# Sheet2.net
KiCad netlist of a schematic drawn in Altium Designer
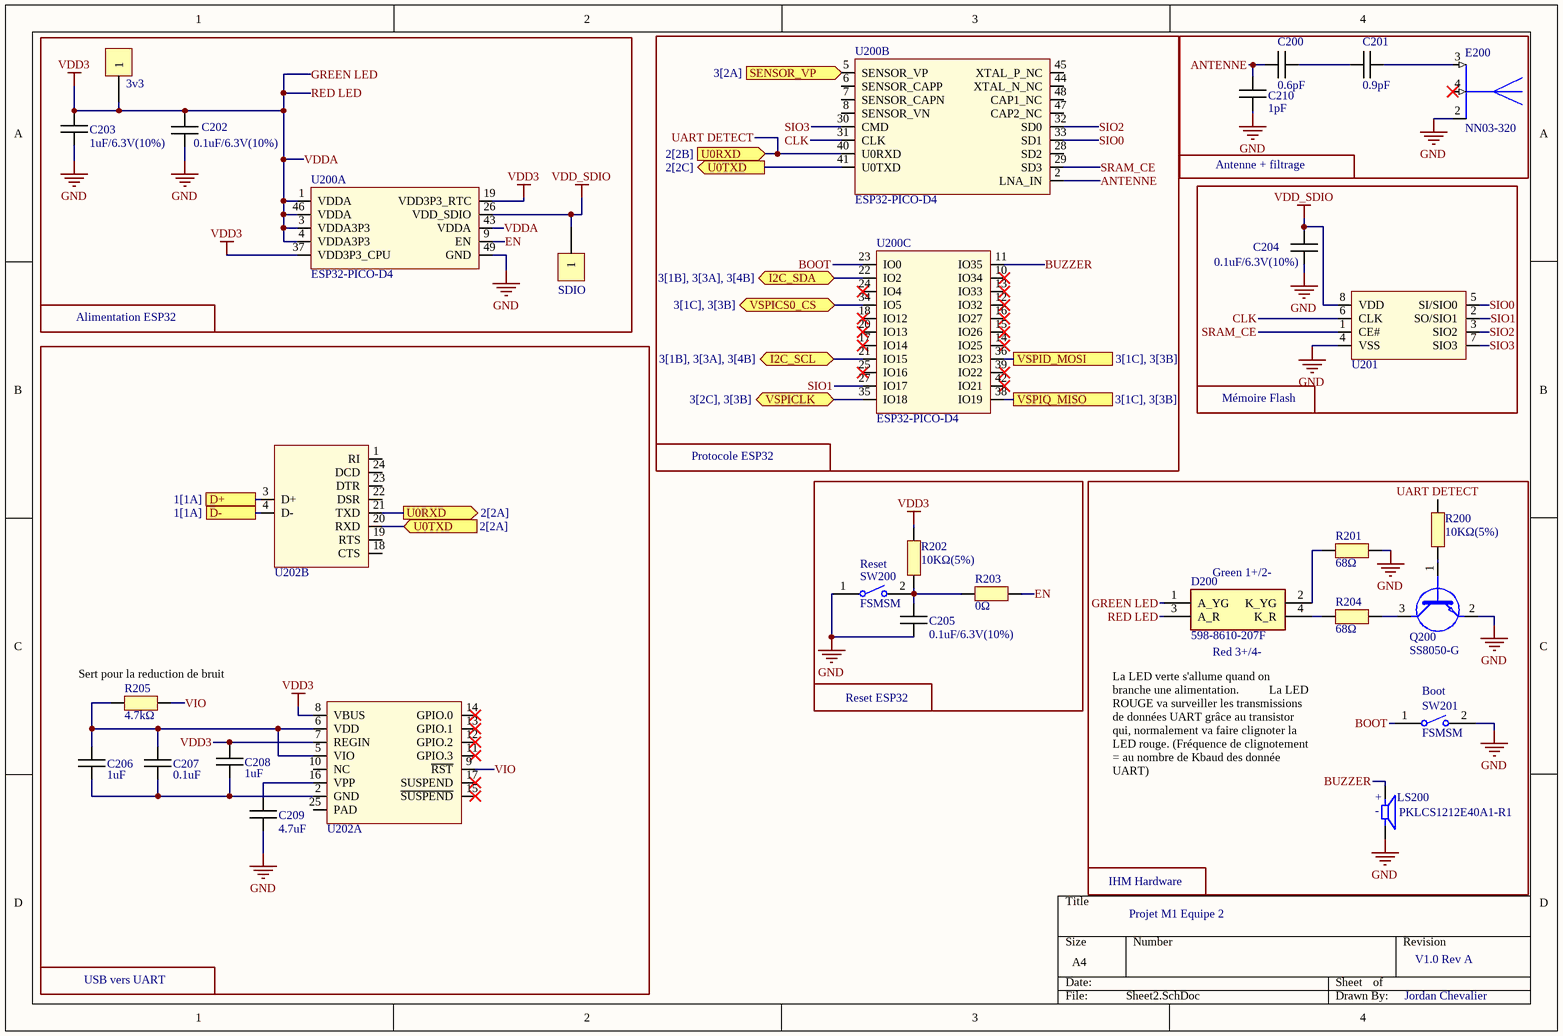
[diagram p0: Sheet2.SchDoc]

(export (version "E")
  (design (tool "Eeschema 10.0.6"))
  (components
    (comp (ref "3v3")
      (value "Plage CMS 10x5")
      (footprint "Plage CMS 10x5")
      (description "Plage de report CMS 10x5mm")
      (libsource (lib "") (part "Plage CMS 10x5_1"))
    )
    (comp (ref "C200")
      (value "0.6pF")
      (footprint "CAPC1005X06N")
      (libsource (lib "SCHLibrary") (part "Capacitor"))
    )
    (comp (ref "C201")
      (value "0.9pF")
      (footprint "CAPC1005X06N")
      (libsource (lib "SCHLibrary") (part "Capacitor"))
    )
    (comp (ref "C202")
      (value "0.1uF/6.3V(10%)")
      (footprint "CAPC1005X06N")
      (libsource (lib "SCHLibrary") (part "Capacitor"))
    )
    (comp (ref "C203")
      (value "1uF/6.3V(10%)")
      (footprint "CAPC1005X06N")
      (libsource (lib "SCHLibrary") (part "Capacitor"))
    )
    (comp (ref "C204")
      (value "0.1uF/6.3V(10%)")
      (footprint "CAPC1005X06N")
      (libsource (lib "SCHLibrary") (part "Capacitor"))
    )
    (comp (ref "C205")
      (value "0.1uF/6.3V(10%)")
      (footprint "CAPC1005X06N")
      (libsource (lib "SCHLibrary") (part "Capacitor"))
    )
    (comp (ref "C206")
      (value "1uF")
      (footprint "CAPC1005X06N")
      (libsource (lib "SCHLibrary") (part "Capacitor"))
    )
    (comp (ref "C207")
      (value "0.1uF")
      (footprint "CAPC1005X06N")
      (libsource (lib "SCHLibrary") (part "Capacitor"))
    )
    (comp (ref "C208")
      (value "1uF")
      (footprint "CAPC1005X06N")
      (libsource (lib "SCHLibrary") (part "Capacitor"))
    )
    (comp (ref "C209")
      (value "4.7uF")
      (footprint "CAPC1005X06N")
      (libsource (lib "SCHLibrary") (part "Capacitor"))
    )
    (comp (ref "C210")
      (value "1pF")
      (footprint "CAPC1005X06N")
      (libsource (lib "SCHLibrary") (part "Capacitor"))
    )
    (comp (ref "D200")
      (value "598-8610-207F")
      (footprint "5988610207F")
      (description "Standard LEDs - SMD Red/Green WC 80/50mcd 645/570nm")
      (fields (field (name "MOUSER PART NUMBER") "645-598-8610-207F"))
      (libsource (lib "SCHLibrary") (part "598-8610-207F"))
    )
    (comp (ref "E200")
      (value "NN03-320")
      (footprint "XCVR_NN03-320")
      (fields (field (name "MOUSER PART NUMBER") "128-NN03-320"))
      (libsource (lib "SCHLibrary") (part "NN03-320"))
    )
    (comp (ref "LS200")
      (value "PKLCS1212E40A1-R1")
      (footprint "SPKR_PKLCS1212E40A1-R1")
      (description "Buzzers Transducer, Externally Driven Piezo 1.5V 2kHz 70dB @ 1.5V, 10cm Surface Mount Solder Pads")
      (fields (field (name "MF") "Murata Electronics"))
      (libsource (lib "SCHLibrary") (part "PKLCS1212E40A1-R1"))
    )
    (comp (ref "Q200")
      (value "SS8050-G")
      (footprint "SS8050-G")
      (description "Bipolar Transistors - BJT NPN TRANSISTOR 1.5A 40V")
      (libsource (lib "SCHLibrary") (part "SS8050-G"))
    )
    (comp (ref "R200")
      (value "10KΩ(5%)")
      (footprint "RESC1005X06N")
      (libsource (lib "SCHLibrary") (part "Resistor"))
    )
    (comp (ref "R201") (value "68Ω") (footprint "RESC1005X06N") (libsource (lib "") (part "Resistor_1")))
    (comp (ref "R202")
      (value "10KΩ(5%)")
      (footprint "RESC1005X06N")
      (libsource (lib "SCHLibrary") (part "Resistor"))
    )
    (comp (ref "R203") (value "0Ω") (footprint "RESC1005X06N") (libsource (lib "") (part "Resistor_1")))
    (comp (ref "R204") (value "68Ω") (footprint "RESC1005X06N") (libsource (lib "") (part "Resistor_1")))
    (comp (ref "R205") (value "4.7kΩ") (footprint "RESC1005X06N") (libsource (lib "") (part "Resistor_1")))
    (comp (ref "SDIO")
      (value "Plage CMS 10x5")
      (footprint "Plage CMS 10x5")
      (description "Plage de report CMS 10x5mm")
      (libsource (lib "SCHLibrary") (part "Plage CMS 10x5"))
    )
    (comp (ref "SW200")
      (value "FSMSM")
      (footprint "TECO-FSMSM-2_V")
      (description "FSMSM Push Button Switch, 50 mA, -35 to 85 degC, 2-Pin SMD, RoHS, Bulk")
      (fields (field (name "MANUFACTURER") "TE Connectivity"))
      (libsource (lib "SCHLibrary") (part "CMP-2000-07511-1"))
    )
    (comp (ref "SW201")
      (value "FSMSM")
      (footprint "TECO-FSMSM-2_V")
      (description "FSMSM Push Button Switch, 50 mA, -35 to 85 degC, 2-Pin SMD, RoHS, Bulk")
      (fields (field (name "MANUFACTURER") "TE Connectivity"))
      (libsource (lib "SCHLibrary") (part "CMP-2000-07511-1"))
    )
    (comp (ref "U200")
      (value "ESP32-PICO-D4")
      (footprint "PQFN50P700X700X104_HS-49N")
      (libsource (lib "SCHLibrary") (part "ESP32"))
    )
    (comp (ref "U201")
      (value "IS66WVS1M8BLL-104NLI")
      (footprint "SOIC127P600X175-8N")
      (description "SRAM 8Mb, SerialRAM, 2.7V-3.6V, 104MHz, 8 pin SOIC 150 mil, RoHS")
      (libsource (lib "SCHLibrary") (part "SRAM"))
    )
    (comp (ref "U202")
      (value "CP2104-F03-GM")
      (footprint "PQFN50P400X400X80_HS-25N")
      (description "USB Bridge, USB to UART USB 2.0 UART Interface 24-QFN (4x4)")
      (libsource (lib "SCHLibrary") (part "USBBridge"))
    )
  )
  (nets
    (net (code "1") (name "/ANTENNE") (class "Default")
      (node (ref "C200") (pin "1") (pinfunction "1_1") (pintype "passive"))
      (node (ref "C210") (pin "1") (pinfunction "1_1") (pintype "passive"))
      (node (ref "U200") (pin "2") (pinfunction "LNA_IN_2") (pintype "passive"))
    )
    (net (code "2") (name "/BOOT") (class "Default")
      (node (ref "SW201") (pin "1") (pinfunction "1_1") (pintype "passive"))
      (node (ref "U200") (pin "23") (pinfunction "IO0_23") (pintype "passive"))
    )
    (net (code "3") (name "/BUZZER") (class "Default")
      (node (ref "LS200") (pin "P") (pinfunction "P_P") (pintype "passive"))
      (node (ref "U200") (pin "11") (pinfunction "IO35_11") (pintype "passive"))
    )
    (net (code "4") (name "/CLK") (class "Default")
      (node (ref "U200") (pin "31") (pinfunction "CLK_31") (pintype "passive"))
      (node (ref "U201") (pin "6") (pinfunction "CLK_6") (pintype "passive"))
    )
    (net (code "5") (name "/D+") (class "Default")
      (node (ref "U202") (pin "3") (pinfunction "D+_3") (pintype "passive"))
    )
    (net (code "6") (name "/D-") (class "Default")
      (node (ref "U202") (pin "4") (pinfunction "D-_4") (pintype "passive"))
    )
    (net (code "7") (name "/EN") (class "Default")
      (node (ref "R203") (pin "2") (pinfunction "2_2") (pintype "passive"))
      (node (ref "U200") (pin "9") (pinfunction "EN_9") (pintype "passive"))
    )
    (net (code "8") (name "/I2C_SCL") (class "Default")
      (node (ref "U200") (pin "21") (pinfunction "IO15_21") (pintype "passive"))
    )
    (net (code "9") (name "/I2C_SDA") (class "Default")
      (node (ref "U200") (pin "22") (pinfunction "IO2_22") (pintype "passive"))
    )
    (net (code "10") (name "/SENSOR_VP") (class "Default")
      (node (ref "U200") (pin "5") (pinfunction "SENSOR_VP_5") (pintype "passive"))
    )
    (net (code "11") (name "/SIO0") (class "Default")
      (node (ref "U200") (pin "33") (pinfunction "SD1_33") (pintype "passive"))
      (node (ref "U201") (pin "5") (pinfunction "SI/SIO0_5") (pintype "passive"))
    )
    (net (code "12") (name "/SIO1") (class "Default")
      (node (ref "U200") (pin "27") (pinfunction "IO17_27") (pintype "passive"))
      (node (ref "U201") (pin "2") (pinfunction "SO/SIO1_2") (pintype "passive"))
    )
    (net (code "13") (name "/SIO2") (class "Default")
      (node (ref "U200") (pin "32") (pinfunction "SD0_32") (pintype "passive"))
      (node (ref "U201") (pin "3") (pinfunction "SIO2_3") (pintype "passive"))
    )
    (net (code "14") (name "/SIO3") (class "Default")
      (node (ref "U200") (pin "30") (pinfunction "CMD_30") (pintype "passive"))
      (node (ref "U201") (pin "7") (pinfunction "SIO3_7") (pintype "passive"))
    )
    (net (code "15") (name "/SRAM_CE") (class "Default")
      (node (ref "U200") (pin "29") (pinfunction "SD3_29") (pintype "passive"))
      (node (ref "U201") (pin "1") (pinfunction "CE#_1") (pintype "passive"))
    )
    (net (code "16") (name "/U0TXD") (class "Default")
      (node (ref "U200") (pin "41") (pinfunction "U0TXD_41") (pintype "passive"))
      (node (ref "U202") (pin "20") (pinfunction "RXD_20") (pintype "passive"))
    )
    (net (code "17") (name "/UART DETECT") (class "Default")
      (node (ref "R200") (pin "2") (pinfunction "2_2") (pintype "passive"))
      (node (ref "U200") (pin "40") (pinfunction "U0RXD_40") (pintype "passive"))
      (node (ref "U202") (pin "21") (pinfunction "TXD_21") (pintype "passive"))
    )
    (net (code "18") (name "/VIO") (class "Default")
      (node (ref "R205") (pin "2") (pinfunction "2_2") (pintype "passive"))
      (node (ref "U202") (pin "9") (pinfunction "~{RST}_9") (pintype "passive"))
    )
    (net (code "19") (name "/VSPICLK") (class "Default")
      (node (ref "U200") (pin "35") (pinfunction "IO18_35") (pintype "passive"))
    )
    (net (code "20") (name "/VSPICS0_CS") (class "Default")
      (node (ref "U200") (pin "34") (pinfunction "IO5_34") (pintype "passive"))
    )
    (net (code "21") (name "/VSPID_MOSI") (class "Default")
      (node (ref "U200") (pin "36") (pinfunction "IO23_36") (pintype "passive"))
    )
    (net (code "22") (name "/VSPIQ_MISO") (class "Default")
      (node (ref "U200") (pin "38") (pinfunction "IO19_38") (pintype "passive"))
    )
    (net (code "23") (name "GND") (class "Default")
      (node (ref "C202") (pin "2") (pinfunction "2_2") (pintype "passive"))
      (node (ref "C203") (pin "2") (pinfunction "2_2") (pintype "passive"))
      (node (ref "C204") (pin "2") (pinfunction "2_2") (pintype "passive"))
      (node (ref "C205") (pin "2") (pinfunction "2_2") (pintype "passive"))
      (node (ref "C209") (pin "2") (pinfunction "2_2") (pintype "passive"))
      (node (ref "C210") (pin "2") (pinfunction "2_2") (pintype "passive"))
      (node (ref "E200") (pin "2") (pinfunction "GROUND_2") (pintype "power_in"))
      (node (ref "LS200") (pin "N") (pinfunction "N_N") (pintype "passive"))
      (node (ref "Q200") (pin "2") (pinfunction "E_2") (pintype "passive"))
      (node (ref "R201") (pin "2") (pinfunction "2_2") (pintype "passive"))
      (node (ref "SW200") (pin "1") (pinfunction "1_1") (pintype "passive"))
      (node (ref "SW201") (pin "2") (pinfunction "2_2") (pintype "passive"))
      (node (ref "U200") (pin "49") (pinfunction "GND_49") (pintype "passive"))
      (node (ref "U201") (pin "4") (pinfunction "VSS_4") (pintype "passive"))
    )
    (net (code "24") (name "Net-(C200-Pad2)") (class "Default")
      (node (ref "C200") (pin "2") (pinfunction "2_2") (pintype "passive"))
      (node (ref "C201") (pin "2") (pinfunction "2_2") (pintype "passive"))
    )
    (net (code "25") (name "Net-(C205-Pad1)") (class "Default")
      (node (ref "C205") (pin "1") (pinfunction "1_1") (pintype "passive"))
      (node (ref "R202") (pin "1") (pinfunction "1_1") (pintype "passive"))
      (node (ref "R203") (pin "1") (pinfunction "1_1") (pintype "passive"))
      (node (ref "SW200") (pin "2") (pinfunction "2_2") (pintype "passive"))
    )
    (net (code "26") (name "Net-(D200-K_R)") (class "Default")
      (node (ref "D200") (pin "4") (pinfunction "K_R_4") (pintype "passive"))
      (node (ref "R204") (pin "1") (pinfunction "1_1") (pintype "passive"))
    )
    (net (code "27") (name "Net-(D200-K_YG)") (class "Default")
      (node (ref "D200") (pin "2") (pinfunction "K_YG_2") (pintype "passive"))
      (node (ref "R201") (pin "1") (pinfunction "1_1") (pintype "passive"))
    )
    (net (code "28") (name "Net-(E200-FEED_BLUETOOTH)") (class "Default")
      (node (ref "C201") (pin "1") (pinfunction "1_1") (pintype "passive"))
      (node (ref "E200") (pin "3") (pinfunction "FEED_BLUETOOTH_3") (pintype "input"))
    )
    (net (code "29") (name "Net-(Q200-B)") (class "Default")
      (node (ref "Q200") (pin "1") (pinfunction "B_1") (pintype "passive"))
      (node (ref "R200") (pin "1") (pinfunction "1_1") (pintype "passive"))
    )
    (net (code "30") (name "Net-(Q200-C)") (class "Default")
      (node (ref "Q200") (pin "3") (pinfunction "C_3") (pintype "passive"))
      (node (ref "R204") (pin "2") (pinfunction "2_2") (pintype "passive"))
    )
    (net (code "31") (name "Net-(U202A-GND)") (class "Default")
      (node (ref "C206") (pin "2") (pinfunction "2_2") (pintype "passive"))
      (node (ref "C207") (pin "2") (pinfunction "2_2") (pintype "passive"))
      (node (ref "C208") (pin "2") (pinfunction "2_2") (pintype "passive"))
      (node (ref "U202") (pin "2") (pinfunction "GND_2") (pintype "passive"))
    )
    (net (code "32") (name "Net-(U202A-VDD)") (class "Default")
      (node (ref "C206") (pin "1") (pinfunction "1_1") (pintype "passive"))
      (node (ref "C207") (pin "1") (pinfunction "1_1") (pintype "passive"))
      (node (ref "R205") (pin "1") (pinfunction "1_1") (pintype "passive"))
      (node (ref "U202") (pin "5") (pinfunction "VIO_5") (pintype "passive"))
      (node (ref "U202") (pin "6") (pinfunction "VDD_6") (pintype "passive"))
    )
    (net (code "33") (name "Net-(U202A-VPP)") (class "Default")
      (node (ref "C209") (pin "1") (pinfunction "1_1") (pintype "passive"))
      (node (ref "U202") (pin "16") (pinfunction "VPP_16") (pintype "passive"))
    )
    (net (code "34") (name "VDD3") (class "Default")
      (node (ref "3v3") (pin "1") (pinfunction "1_1") (pintype "passive"))
      (node (ref "C202") (pin "1") (pinfunction "1_1") (pintype "passive"))
      (node (ref "C203") (pin "1") (pinfunction "1_1") (pintype "passive"))
      (node (ref "C208") (pin "1") (pinfunction "1_1") (pintype "passive"))
      (node (ref "D200") (pin "1") (pinfunction "A_YG_1") (pintype "passive"))
      (node (ref "D200") (pin "3") (pinfunction "A_R_3") (pintype "passive"))
      (node (ref "R202") (pin "2") (pinfunction "2_2") (pintype "passive"))
      (node (ref "U200") (pin "1") (pinfunction "VDDA_1") (pintype "passive"))
      (node (ref "U200") (pin "19") (pinfunction "VDD3P3_RTC_19") (pintype "passive"))
      (node (ref "U200") (pin "3") (pinfunction "VDDA3P3_3") (pintype "passive"))
      (node (ref "U200") (pin "37") (pinfunction "VDD3P3_CPU_37") (pintype "passive"))
      (node (ref "U200") (pin "4") (pinfunction "VDDA3P3_4") (pintype "passive"))
      (node (ref "U200") (pin "43") (pinfunction "VDDA_43") (pintype "passive"))
      (node (ref "U200") (pin "46") (pinfunction "VDDA_46") (pintype "passive"))
      (node (ref "U202") (pin "7") (pinfunction "REGIN_7") (pintype "passive"))
      (node (ref "U202") (pin "8") (pinfunction "VBUS_8") (pintype "passive"))
    )
    (net (code "35") (name "VDD_SDIO") (class "Default")
      (node (ref "C204") (pin "1") (pinfunction "1_1") (pintype "passive"))
      (node (ref "SDIO") (pin "1") (pinfunction "1_1") (pintype "passive"))
      (node (ref "U200") (pin "26") (pinfunction "VDD_SDIO_26") (pintype "passive"))
      (node (ref "U201") (pin "8") (pinfunction "VDD_8") (pintype "passive"))
    )
    (net (code "36") (name "unconnected-(E200-FEED_GNSS-Pad4)") (class "Default")
      (node (ref "E200") (pin "4") (pinfunction "FEED_GNSS_4") (pintype "input+no_connect"))
    )
    (net (code "37") (name "unconnected-(U200B-CAP1_NC-Pad48)") (class "Default")
      (node (ref "U200") (pin "48") (pinfunction "CAP1_NC_48") (pintype "passive"))
    )
    (net (code "38") (name "unconnected-(U200B-CAP2_NC-Pad47)") (class "Default")
      (node (ref "U200") (pin "47") (pinfunction "CAP2_NC_47") (pintype "passive"))
    )
    (net (code "39") (name "unconnected-(U200B-SD2-Pad28)") (class "Default")
      (node (ref "U200") (pin "28") (pinfunction "SD2_28") (pintype "passive"))
    )
    (net (code "40") (name "unconnected-(U200B-SENSOR_CAPN-Pad7)") (class "Default")
      (node (ref "U200") (pin "7") (pinfunction "SENSOR_CAPN_7") (pintype "passive"))
    )
    (net (code "41") (name "unconnected-(U200B-SENSOR_CAPP-Pad6)") (class "Default")
      (node (ref "U200") (pin "6") (pinfunction "SENSOR_CAPP_6") (pintype "passive"))
    )
    (net (code "42") (name "unconnected-(U200B-SENSOR_VN-Pad8)") (class "Default")
      (node (ref "U200") (pin "8") (pinfunction "SENSOR_VN_8") (pintype "passive"))
    )
    (net (code "43") (name "unconnected-(U200B-XTAL_N_NC-Pad44)") (class "Default")
      (node (ref "U200") (pin "44") (pinfunction "XTAL_N_NC_44") (pintype "passive"))
    )
    (net (code "44") (name "unconnected-(U200B-XTAL_P_NC-Pad45)") (class "Default")
      (node (ref "U200") (pin "45") (pinfunction "XTAL_P_NC_45") (pintype "passive"))
    )
    (net (code "45") (name "unconnected-(U200C-IO4-Pad24)") (class "Default")
      (node (ref "U200") (pin "24") (pinfunction "IO4_24") (pintype "passive+no_connect"))
    )
    (net (code "46") (name "unconnected-(U200C-IO12-Pad18)") (class "Default")
      (node (ref "U200") (pin "18") (pinfunction "IO12_18") (pintype "passive+no_connect"))
    )
    (net (code "47") (name "unconnected-(U200C-IO13-Pad20)") (class "Default")
      (node (ref "U200") (pin "20") (pinfunction "IO13_20") (pintype "passive+no_connect"))
    )
    (net (code "48") (name "unconnected-(U200C-IO14-Pad17)") (class "Default")
      (node (ref "U200") (pin "17") (pinfunction "IO14_17") (pintype "passive+no_connect"))
    )
    (net (code "49") (name "unconnected-(U200C-IO16-Pad25)") (class "Default")
      (node (ref "U200") (pin "25") (pinfunction "IO16_25") (pintype "passive+no_connect"))
    )
    (net (code "50") (name "unconnected-(U200C-IO21-Pad42)") (class "Default")
      (node (ref "U200") (pin "42") (pinfunction "IO21_42") (pintype "passive+no_connect"))
    )
    (net (code "51") (name "unconnected-(U200C-IO22-Pad39)") (class "Default")
      (node (ref "U200") (pin "39") (pinfunction "IO22_39") (pintype "passive+no_connect"))
    )
    (net (code "52") (name "unconnected-(U200C-IO25-Pad14)") (class "Default")
      (node (ref "U200") (pin "14") (pinfunction "IO25_14") (pintype "passive+no_connect"))
    )
    (net (code "53") (name "unconnected-(U200C-IO26-Pad15)") (class "Default")
      (node (ref "U200") (pin "15") (pinfunction "IO26_15") (pintype "passive+no_connect"))
    )
    (net (code "54") (name "unconnected-(U200C-IO27-Pad16)") (class "Default")
      (node (ref "U200") (pin "16") (pinfunction "IO27_16") (pintype "passive+no_connect"))
    )
    (net (code "55") (name "unconnected-(U200C-IO32-Pad12)") (class "Default")
      (node (ref "U200") (pin "12") (pinfunction "IO32_12") (pintype "passive+no_connect"))
    )
    (net (code "56") (name "unconnected-(U200C-IO33-Pad13)") (class "Default")
      (node (ref "U200") (pin "13") (pinfunction "IO33_13") (pintype "passive+no_connect"))
    )
    (net (code "57") (name "unconnected-(U200C-IO34-Pad10)") (class "Default")
      (node (ref "U200") (pin "10") (pinfunction "IO34_10") (pintype "passive+no_connect"))
    )
    (net (code "58") (name "unconnected-(U202A-GPIO.0-Pad14)") (class "Default")
      (node (ref "U202") (pin "14") (pinfunction "GPIO.0_14") (pintype "passive+no_connect"))
    )
    (net (code "59") (name "unconnected-(U202A-GPIO.1-Pad13)") (class "Default")
      (node (ref "U202") (pin "13") (pinfunction "GPIO.1_13") (pintype "passive+no_connect"))
    )
    (net (code "60") (name "unconnected-(U202A-GPIO.2-Pad12)") (class "Default")
      (node (ref "U202") (pin "12") (pinfunction "GPIO.2_12") (pintype "passive+no_connect"))
    )
    (net (code "61") (name "unconnected-(U202A-GPIO.3-Pad11)") (class "Default")
      (node (ref "U202") (pin "11") (pinfunction "GPIO.3_11") (pintype "passive+no_connect"))
    )
    (net (code "62") (name "unconnected-(U202A-NC-Pad10)") (class "Default")
      (node (ref "U202") (pin "10") (pinfunction "NC_10") (pintype "passive"))
    )
    (net (code "63") (name "unconnected-(U202A-PAD-Pad25)") (class "Default")
      (node (ref "U202") (pin "25") (pinfunction "PAD_25") (pintype "passive"))
    )
    (net (code "64") (name "unconnected-(U202A-SUSPEND-Pad17)") (class "Default")
      (node (ref "U202") (pin "17") (pinfunction "SUSPEND_17") (pintype "passive+no_connect"))
    )
    (net (code "65") (name "unconnected-(U202A-~{SUSPEND}-Pad15)") (class "Default")
      (node (ref "U202") (pin "15") (pinfunction "~{SUSPEND}_15") (pintype "passive+no_connect"))
    )
    (net (code "66") (name "unconnected-(U202B-CTS-Pad18)") (class "Default")
      (node (ref "U202") (pin "18") (pinfunction "CTS_18") (pintype "passive"))
    )
    (net (code "67") (name "unconnected-(U202B-DCD-Pad24)") (class "Default")
      (node (ref "U202") (pin "24") (pinfunction "DCD_24") (pintype "passive"))
    )
    (net (code "68") (name "unconnected-(U202B-DSR-Pad22)") (class "Default")
      (node (ref "U202") (pin "22") (pinfunction "DSR_22") (pintype "passive"))
    )
    (net (code "69") (name "unconnected-(U202B-DTR-Pad23)") (class "Default")
      (node (ref "U202") (pin "23") (pinfunction "DTR_23") (pintype "passive"))
    )
    (net (code "70") (name "unconnected-(U202B-RI-Pad1)") (class "Default")
      (node (ref "U202") (pin "1") (pinfunction "RI_1") (pintype "passive"))
    )
    (net (code "71") (name "unconnected-(U202B-RTS-Pad19)") (class "Default")
      (node (ref "U202") (pin "19") (pinfunction "RTS_19") (pintype "passive"))
    )
  )
)
